# DSO_Control.net
KiCad netlist of a schematic drawn in Altium Designer
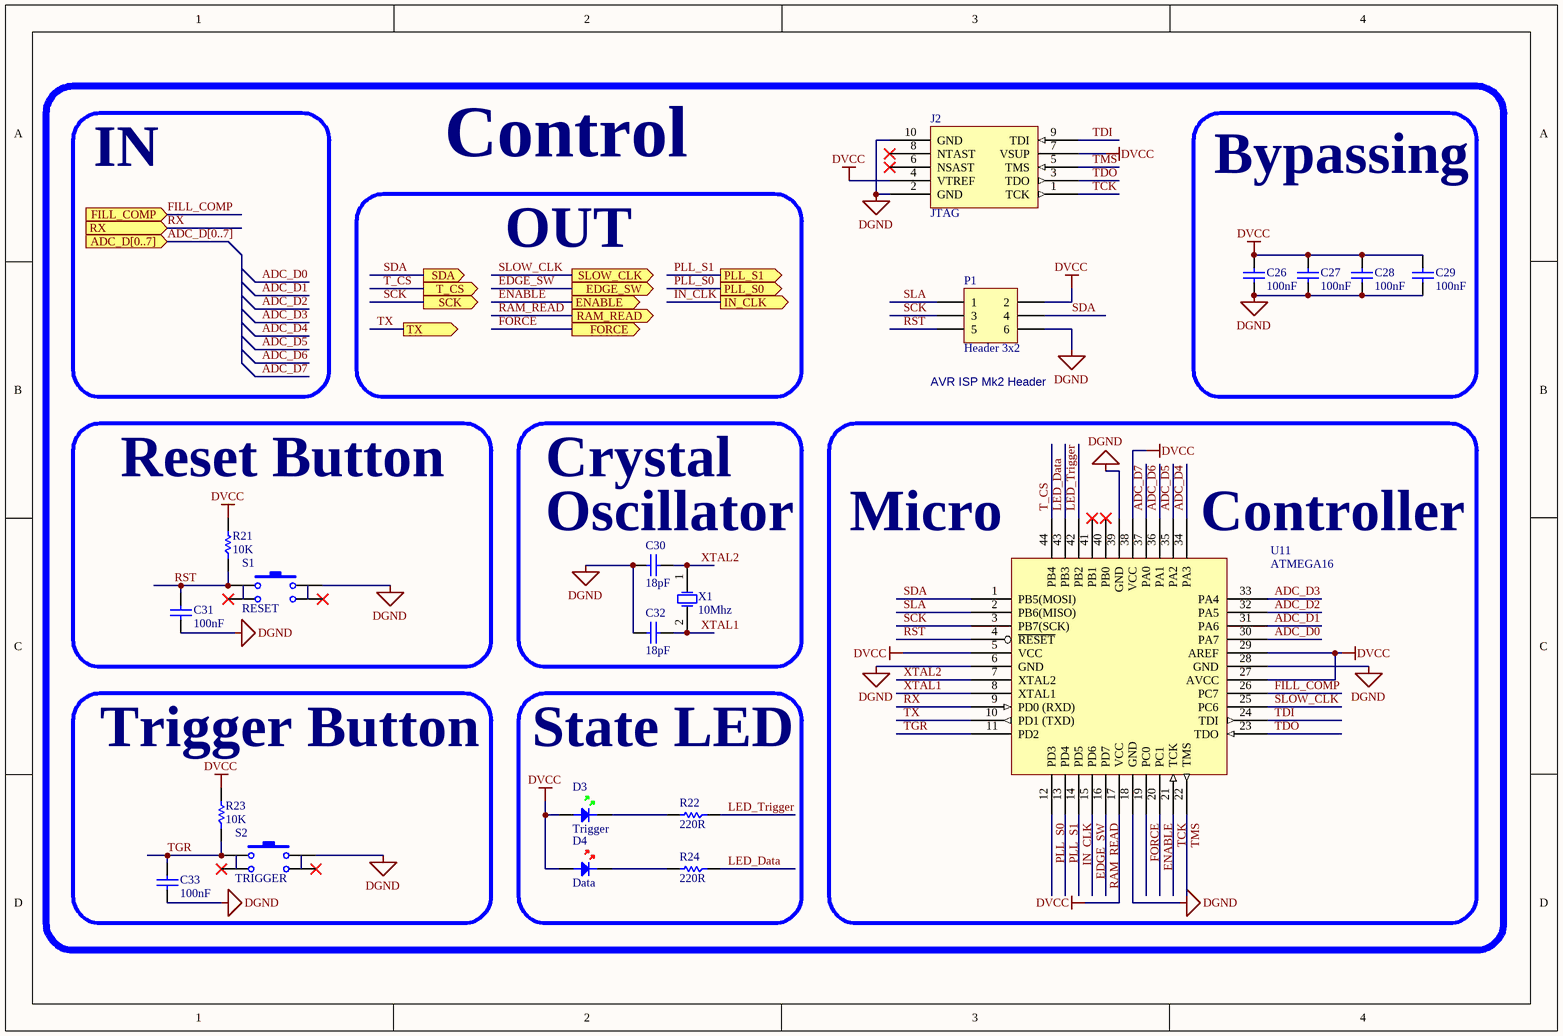
[diagram p0: DSO_Control.SchDoc]

(export (version "E")
  (design (tool "Eeschema 10.0.6"))
  (components
    (comp (ref "C26")
      (value "100nF")
      (footprint "0805C")
      (description "Capacitor")
      (fields (field (name "REVIEWED BY") "RM - 2018/08/05"))
      (libsource (lib "DSO") (part "C"))
    )
    (comp (ref "C27")
      (value "100nF")
      (footprint "0805C")
      (description "Capacitor")
      (fields (field (name "REVIEWED BY") "RM - 2018/08/05"))
      (libsource (lib "DSO") (part "C"))
    )
    (comp (ref "C28")
      (value "100nF")
      (footprint "0805C")
      (description "Capacitor")
      (fields (field (name "REVIEWED BY") "RM - 2018/08/05"))
      (libsource (lib "DSO") (part "C"))
    )
    (comp (ref "C29")
      (value "100nF")
      (footprint "0805C")
      (description "Capacitor")
      (fields (field (name "REVIEWED BY") "RM - 2018/08/05"))
      (libsource (lib "DSO") (part "C"))
    )
    (comp (ref "C30")
      (value "18pF")
      (footprint "0805C")
      (description "Capacitor")
      (fields (field (name "REVIEWED BY") "RM - 2018/08/05"))
      (libsource (lib "DSO") (part "C"))
    )
    (comp (ref "C31")
      (value "100nF")
      (footprint "0805C")
      (description "Capacitor")
      (fields (field (name "REVIEWED BY") "RM - 2018/08/05"))
      (libsource (lib "DSO") (part "C"))
    )
    (comp (ref "C32")
      (value "18pF")
      (footprint "0805C")
      (description "Capacitor")
      (fields (field (name "REVIEWED BY") "RM - 2018/08/05"))
      (libsource (lib "DSO") (part "C"))
    )
    (comp (ref "C33")
      (value "100nF")
      (footprint "0805C")
      (description "Capacitor")
      (fields (field (name "REVIEWED BY") "RM - 2018/08/05"))
      (libsource (lib "DSO") (part "C"))
    )
    (comp (ref "D3")
      (value "Trigger")
      (footprint "0805D-GREEN")
      (description "Light Emitting Diode")
      (fields (field (name "REVIEWED BY") "RM - 2018/08/05"))
      (libsource (lib "DSO") (part "LED GREEN"))
    )
    (comp (ref "D4")
      (value "Data")
      (footprint "0805D-RED")
      (description "Light Emitting Diode")
      (fields (field (name "REVIEWED BY") "RM - 2018/08/05"))
      (libsource (lib "DSO") (part "LED RED"))
    )
    (comp (ref "J2")
      (value "JTAG")
      (footprint "BOXEDVERT10")
      (description "JTAG_CON")
      (fields (field (name "REVIEWED BY") "RM - 2018/08/05"))
      (libsource (lib "DSO") (part "JTAG_CON"))
    )
    (comp (ref "P1")
      (value "Header 3x2")
      (footprint "HDR3x2")
      (description "Header, 5-Pin")
      (fields (field (name "REVIEWED BY") "RM - 2018/08/05"))
      (libsource (lib "DSO") (part "Header 3x2"))
    )
    (comp (ref "R21")
      (value "10K")
      (footprint "0805")
      (description "Resistor")
      (fields (field (name "REVIEWED BY") "RM - 2018/08/05"))
      (libsource (lib "DSO") (part "R"))
    )
    (comp (ref "R22")
      (value "220R")
      (footprint "0805")
      (description "Resistor")
      (fields (field (name "REVIEWED BY") "RM - 2018/08/05"))
      (libsource (lib "DSO") (part "R"))
    )
    (comp (ref "R23")
      (value "10K")
      (footprint "0805")
      (description "Resistor")
      (fields (field (name "REVIEWED BY") "RM - 2018/08/05"))
      (libsource (lib "DSO") (part "R"))
    )
    (comp (ref "R24")
      (value "220R")
      (footprint "0805")
      (description "Resistor")
      (fields (field (name "REVIEWED BY") "RM - 2018/08/05"))
      (libsource (lib "DSO") (part "R"))
    )
    (comp (ref "S1")
      (value "RESET")
      (footprint "SPST PB SWITCH SMD")
      (description "Momentary Push Button Switch 1P 1T 2pins")
      (fields (field (name "REVIEWED BY") "RM - 2018/08/05"))
      (libsource (lib "DSO") (part "SW_PB_1P1T4"))
    )
    (comp (ref "S2")
      (value "TRIGGER")
      (footprint "SPST PB SWITCH SMD")
      (description "Momentary Push Button Switch 1P 1T 2pins")
      (fields (field (name "REVIEWED BY") "RM - 2018/08/05"))
      (libsource (lib "DSO") (part "SW_PB_1P1T4"))
    )
    (comp (ref "U11")
      (value "ATMEGA16")
      (footprint "QFP-48")
      (description "ATMEGA16 Microcontroller")
      (fields (field (name "REVIEWED BY") "RM - 2018/08/05"))
      (libsource (lib "DSO") (part "ATMEGA16"))
    )
    (comp (ref "X1")
      (value "10Mhz")
      (footprint "XTAL_FLAT_SMD")
      (description "Crystal Oscillator")
      (fields (field (name "REVIEWED BY") "RM - 2018/08/05"))
      (libsource (lib "DSO") (part "XTAL"))
    )
  )
  (nets
    (net (code "1") (name "/ADC_D0") (class "Default")
      (node (ref "U11") (pin "30") (pinfunction "PA7_30") (pintype "passive"))
    )
    (net (code "2") (name "/ADC_D1") (class "Default")
      (node (ref "U11") (pin "31") (pinfunction "PA6_31") (pintype "passive"))
    )
    (net (code "3") (name "/ADC_D2") (class "Default")
      (node (ref "U11") (pin "32") (pinfunction "PA5_32") (pintype "passive"))
    )
    (net (code "4") (name "/ADC_D3") (class "Default")
      (node (ref "U11") (pin "33") (pinfunction "PA4_33") (pintype "passive"))
    )
    (net (code "5") (name "/ADC_D4") (class "Default")
      (node (ref "U11") (pin "34") (pinfunction "PA3_34") (pintype "passive"))
    )
    (net (code "6") (name "/ADC_D5") (class "Default")
      (node (ref "U11") (pin "35") (pinfunction "PA2_35") (pintype "passive"))
    )
    (net (code "7") (name "/ADC_D6") (class "Default")
      (node (ref "U11") (pin "36") (pinfunction "PA1_36") (pintype "passive"))
    )
    (net (code "8") (name "/ADC_D7") (class "Default")
      (node (ref "U11") (pin "37") (pinfunction "PA0_37") (pintype "passive"))
    )
    (net (code "10") (name "/EDGE_SW") (class "Default")
      (node (ref "U11") (pin "15") (pinfunction "PD6_15") (pintype "passive"))
    )
    (net (code "11") (name "/ENABLE") (class "Default")
      (node (ref "U11") (pin "20") (pinfunction "PC1_20") (pintype "passive"))
    )
    (net (code "12") (name "/FILL_COMP") (class "Default")
      (node (ref "U11") (pin "26") (pinfunction "PC7_26") (pintype "passive"))
    )
    (net (code "13") (name "/FORCE") (class "Default")
      (node (ref "U11") (pin "19") (pinfunction "PC0_19") (pintype "passive"))
    )
    (net (code "14") (name "/IN_CLK") (class "Default")
      (node (ref "U11") (pin "14") (pinfunction "PD5_14") (pintype "passive"))
    )
    (net (code "15") (name "/LED_Data") (class "Default")
      (node (ref "R24") (pin "1") (pintype "passive"))
      (node (ref "U11") (pin "43") (pinfunction "PB3_43") (pintype "passive"))
    )
    (net (code "16") (name "/LED_Trigger") (class "Default")
      (node (ref "R22") (pin "1") (pintype "passive"))
      (node (ref "U11") (pin "42") (pinfunction "PB2_42") (pintype "passive"))
    )
    (net (code "17") (name "/PLL_S0") (class "Default")
      (node (ref "U11") (pin "12") (pinfunction "PD3_12") (pintype "passive"))
    )
    (net (code "18") (name "/PLL_S1") (class "Default")
      (node (ref "U11") (pin "13") (pinfunction "PD4_13") (pintype "passive"))
    )
    (net (code "19") (name "/RAM_READ") (class "Default")
      (node (ref "U11") (pin "16") (pinfunction "PD7_16") (pintype "passive"))
    )
    (net (code "20") (name "/RST") (class "Default")
      (node (ref "C31") (pin "2") (pinfunction "2_2") (pintype "passive"))
      (node (ref "P1") (pin "5") (pinfunction "5_5") (pintype "passive"))
      (node (ref "R21") (pin "1") (pintype "passive"))
      (node (ref "S1") (pin "1") (pinfunction "1_1") (pintype "passive"))
      (node (ref "U11") (pin "4") (pinfunction "~{RESET}_4") (pintype "passive"))
    )
    (net (code "21") (name "/RX") (class "Default")
      (node (ref "U11") (pin "9") (pinfunction "PD0_(RXD)_9") (pintype "input"))
    )
    (net (code "22") (name "/SCK") (class "Default")
      (node (ref "P1") (pin "3") (pinfunction "3_3") (pintype "passive"))
      (node (ref "U11") (pin "3") (pinfunction "PB7(SCK)_3") (pintype "passive"))
    )
    (net (code "23") (name "/SDA") (class "Default")
      (node (ref "P1") (pin "4") (pinfunction "4_4") (pintype "passive"))
      (node (ref "U11") (pin "1") (pinfunction "PB5(MOSI)_1") (pintype "passive"))
    )
    (net (code "24") (name "/SLA") (class "Default")
      (node (ref "P1") (pin "1") (pinfunction "1_1") (pintype "passive"))
      (node (ref "U11") (pin "2") (pinfunction "PB6(MISO)_2") (pintype "passive"))
    )
    (net (code "25") (name "/SLOW_CLK") (class "Default")
      (node (ref "U11") (pin "25") (pinfunction "PC6_25") (pintype "passive"))
    )
    (net (code "26") (name "/TCK") (class "Default")
      (node (ref "J2") (pin "1") (pinfunction "TCK_1") (pintype "output"))
      (node (ref "U11") (pin "21") (pinfunction "TCK_21") (pintype "input"))
    )
    (net (code "27") (name "/TDI") (class "Default")
      (node (ref "J2") (pin "9") (pinfunction "TDI_9") (pintype "input"))
      (node (ref "U11") (pin "24") (pinfunction "TDI_24") (pintype "output"))
    )
    (net (code "28") (name "/TDO") (class "Default")
      (node (ref "J2") (pin "3") (pinfunction "TDO_3") (pintype "output"))
      (node (ref "U11") (pin "23") (pinfunction "TDO_23") (pintype "input"))
    )
    (net (code "29") (name "/TGR") (class "Default")
      (node (ref "C33") (pin "2") (pinfunction "2_2") (pintype "passive"))
      (node (ref "R23") (pin "1") (pintype "passive"))
      (node (ref "S2") (pin "1") (pinfunction "1_1") (pintype "passive"))
      (node (ref "U11") (pin "11") (pinfunction "PD2_11") (pintype "passive"))
    )
    (net (code "30") (name "/TMS") (class "Default")
      (node (ref "J2") (pin "5") (pinfunction "TMS_5") (pintype "input"))
      (node (ref "U11") (pin "22") (pinfunction "TMS_22") (pintype "output"))
    )
    (net (code "31") (name "/TX") (class "Default")
      (node (ref "U11") (pin "10") (pinfunction "PD1_(TXD)_10") (pintype "output"))
    )
    (net (code "32") (name "/T_CS") (class "Default")
      (node (ref "U11") (pin "44") (pinfunction "PB4_44") (pintype "passive"))
    )
    (net (code "33") (name "/XTAL1") (class "Default")
      (node (ref "C32") (pin "1") (pinfunction "1_1") (pintype "passive"))
      (node (ref "U11") (pin "8") (pinfunction "XTAL1_8") (pintype "passive"))
      (node (ref "X1") (pin "2") (pinfunction "OSC2_2") (pintype "passive"))
    )
    (net (code "34") (name "/XTAL2") (class "Default")
      (node (ref "C30") (pin "1") (pinfunction "1_1") (pintype "passive"))
      (node (ref "U11") (pin "7") (pinfunction "XTAL2_7") (pintype "passive"))
      (node (ref "X1") (pin "1") (pinfunction "OSC1_1") (pintype "passive"))
    )
    (net (code "35") (name "DGND") (class "Default")
      (node (ref "C26") (pin "2") (pinfunction "2_2") (pintype "passive"))
      (node (ref "C27") (pin "2") (pinfunction "2_2") (pintype "passive"))
      (node (ref "C28") (pin "2") (pinfunction "2_2") (pintype "passive"))
      (node (ref "C29") (pin "2") (pinfunction "2_2") (pintype "passive"))
      (node (ref "C30") (pin "2") (pinfunction "2_2") (pintype "passive"))
      (node (ref "C31") (pin "1") (pinfunction "1_1") (pintype "passive"))
      (node (ref "C32") (pin "2") (pinfunction "2_2") (pintype "passive"))
      (node (ref "C33") (pin "1") (pinfunction "1_1") (pintype "passive"))
      (node (ref "J2") (pin "10") (pinfunction "GND_10") (pintype "passive"))
      (node (ref "J2") (pin "2") (pinfunction "GND_2") (pintype "passive"))
      (node (ref "P1") (pin "6") (pinfunction "6_6") (pintype "passive"))
      (node (ref "S1") (pin "2") (pinfunction "2_2") (pintype "passive"))
      (node (ref "S2") (pin "2") (pinfunction "2_2") (pintype "passive"))
      (node (ref "U11") (pin "18") (pinfunction "GND_18") (pintype "passive"))
      (node (ref "U11") (pin "28") (pinfunction "GND_28") (pintype "passive"))
      (node (ref "U11") (pin "39") (pinfunction "GND_39") (pintype "passive"))
      (node (ref "U11") (pin "6") (pinfunction "GND_6") (pintype "passive"))
    )
    (net (code "36") (name "DVCC") (class "Default")
      (node (ref "C26") (pin "1") (pinfunction "1_1") (pintype "passive"))
      (node (ref "C27") (pin "1") (pinfunction "1_1") (pintype "passive"))
      (node (ref "C28") (pin "1") (pinfunction "1_1") (pintype "passive"))
      (node (ref "C29") (pin "1") (pinfunction "1_1") (pintype "passive"))
      (node (ref "D3") (pin "A") (pinfunction "A_A") (pintype "passive"))
      (node (ref "D4") (pin "A") (pinfunction "A_A") (pintype "passive"))
      (node (ref "J2") (pin "4") (pinfunction "VTREF_4") (pintype "power_in"))
      (node (ref "J2") (pin "7") (pinfunction "VSUP_7") (pintype "passive"))
      (node (ref "P1") (pin "2") (pinfunction "2_2") (pintype "passive"))
      (node (ref "R21") (pin "2") (pintype "passive"))
      (node (ref "R23") (pin "2") (pintype "passive"))
      (node (ref "U11") (pin "17") (pinfunction "VCC_17") (pintype "passive"))
      (node (ref "U11") (pin "27") (pinfunction "AVCC_27") (pintype "passive"))
      (node (ref "U11") (pin "29") (pinfunction "AREF_29") (pintype "passive"))
      (node (ref "U11") (pin "38") (pinfunction "VCC_38") (pintype "passive"))
      (node (ref "U11") (pin "5") (pinfunction "VCC_5") (pintype "passive"))
    )
    (net (code "37") (name "Net-(D3-PadK)") (class "Default")
      (node (ref "D3") (pin "K") (pinfunction "K_K") (pintype "passive"))
      (node (ref "R22") (pin "2") (pintype "passive"))
    )
    (net (code "38") (name "Net-(D4-PadK)") (class "Default")
      (node (ref "D4") (pin "K") (pinfunction "K_K") (pintype "passive"))
      (node (ref "R24") (pin "2") (pintype "passive"))
    )
    (net (code "39") (name "unconnected-(J2-NSAST-Pad6)") (class "Default")
      (node (ref "J2") (pin "6") (pinfunction "NSAST_6") (pintype "passive+no_connect"))
    )
    (net (code "40") (name "unconnected-(J2-NTAST-Pad8)") (class "Default")
      (node (ref "J2") (pin "8") (pinfunction "NTAST_8") (pintype "passive+no_connect"))
    )
    (net (code "41") (name "unconnected-(S1-Pad3)") (class "Default")
      (node (ref "S1") (pin "3") (pinfunction "3_3") (pintype "passive+no_connect"))
    )
    (net (code "42") (name "unconnected-(S1-Pad4)") (class "Default")
      (node (ref "S1") (pin "4") (pinfunction "4_4") (pintype "passive+no_connect"))
    )
    (net (code "43") (name "unconnected-(S2-Pad3)") (class "Default")
      (node (ref "S2") (pin "3") (pinfunction "3_3") (pintype "passive+no_connect"))
    )
    (net (code "44") (name "unconnected-(S2-Pad4)") (class "Default")
      (node (ref "S2") (pin "4") (pinfunction "4_4") (pintype "passive+no_connect"))
    )
    (net (code "45") (name "unconnected-(U11-PB0-Pad40)") (class "Default")
      (node (ref "U11") (pin "40") (pinfunction "PB0_40") (pintype "passive+no_connect"))
    )
    (net (code "46") (name "unconnected-(U11-PB1-Pad41)") (class "Default")
      (node (ref "U11") (pin "41") (pinfunction "PB1_41") (pintype "passive+no_connect"))
    )
  )
)
